# PiPowerHat.net
KiCad netlist of a schematic drawn in EAGLE
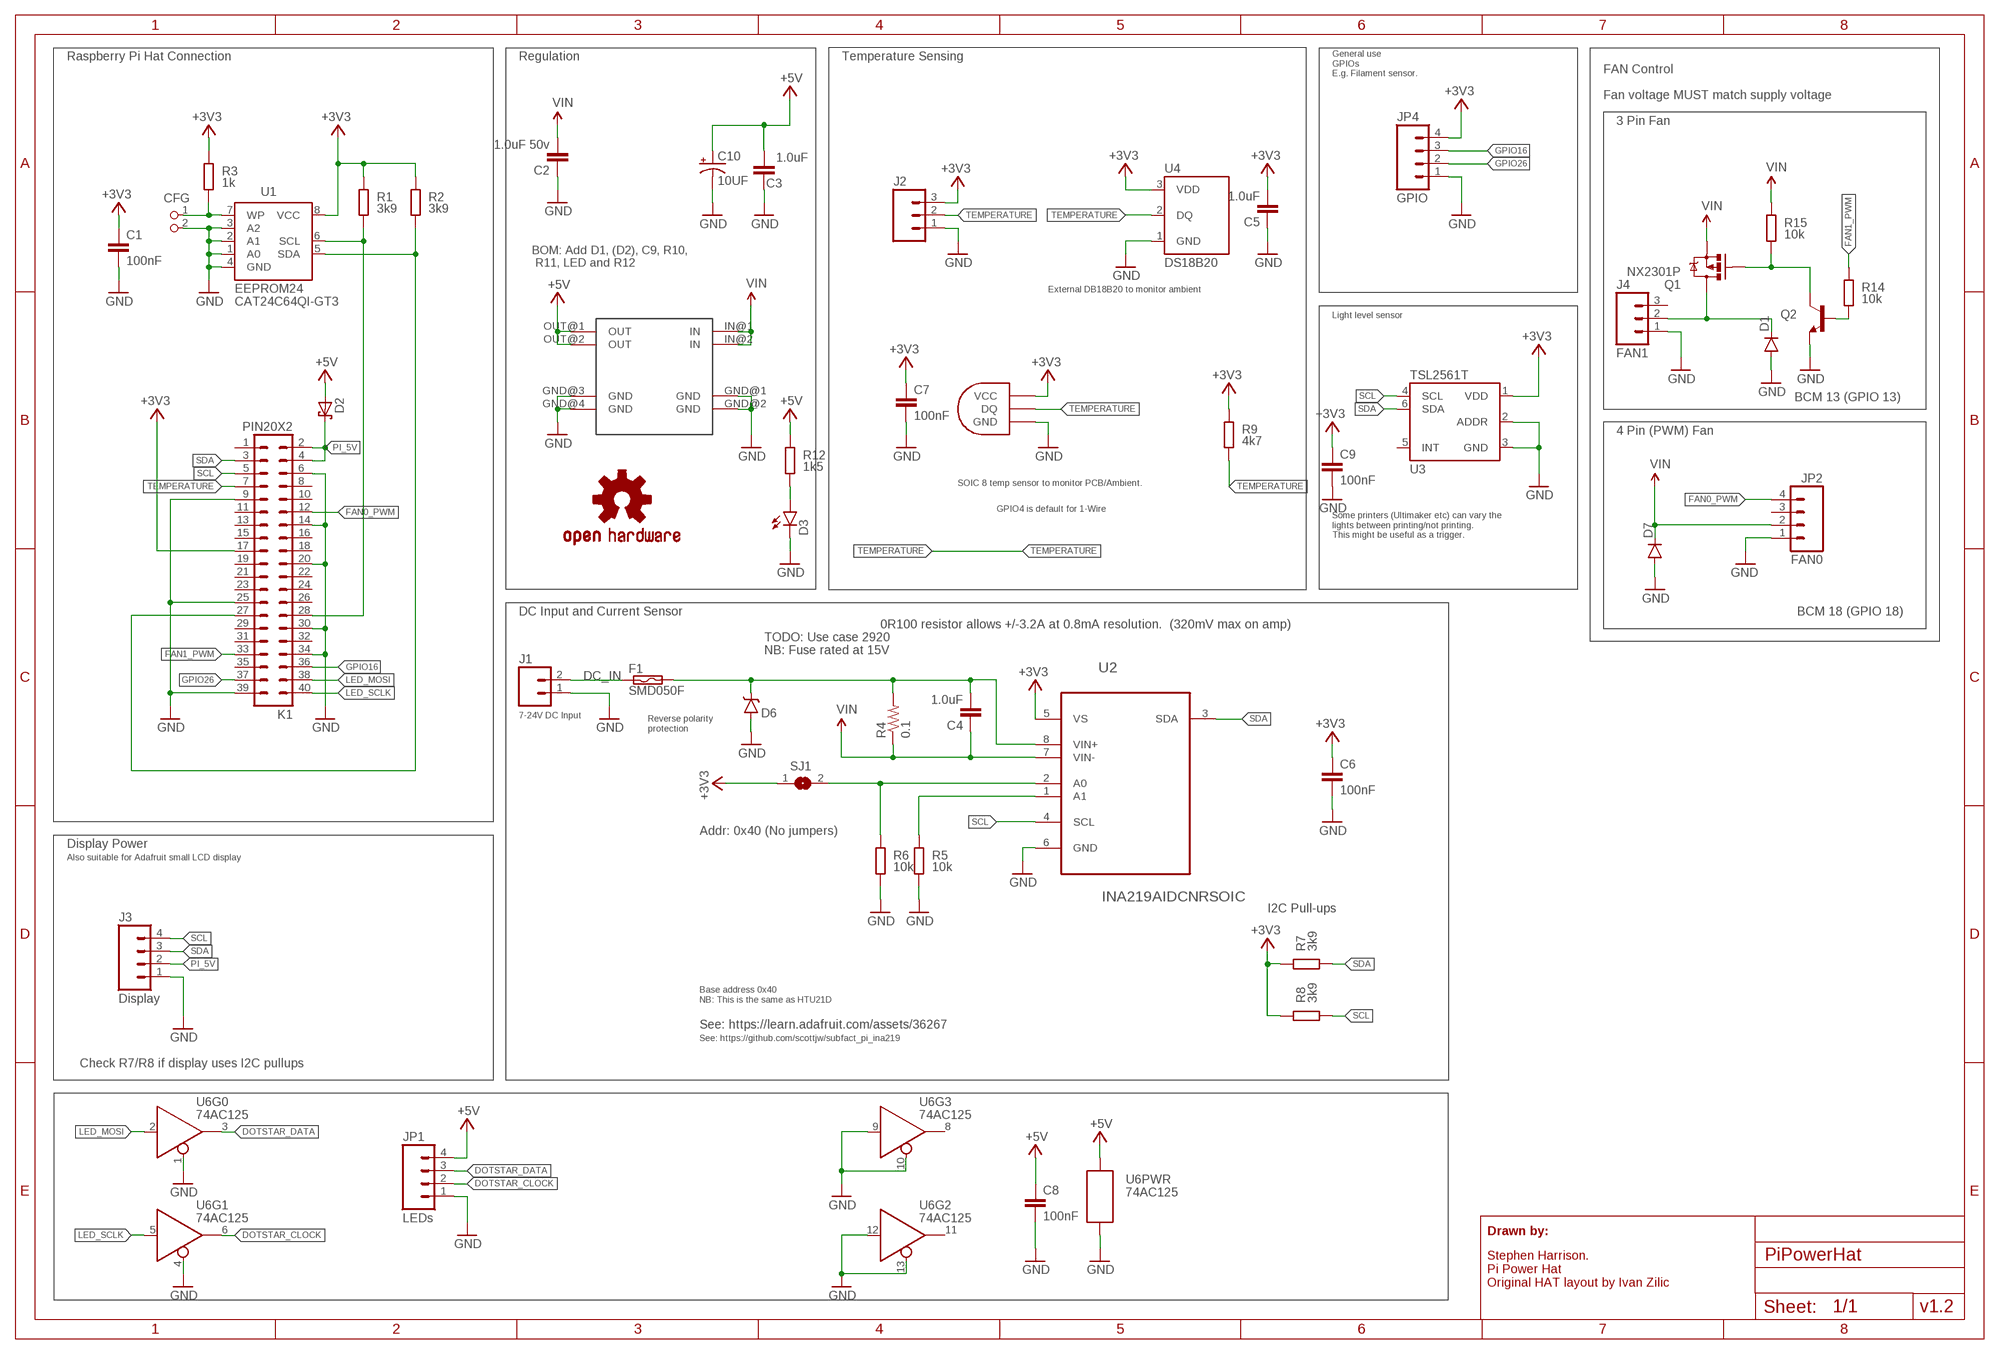
[diagram p0: schematic, sheet 1]

(export (version "E")
  (design (tool "Eeschema 10.0.6"))
  (components
    (comp (ref "C1")
      (value "100nF")
      (footprint "eagle-import:C0805K")
      (libsource (lib "eagle-import") (part "C-EUC0805K"))
    )
    (comp (ref "C2")
      (value "1.0uF 50v")
      (footprint "eagle-import:0805-CAP")
      (libsource (lib "eagle-import") (part "1.0UF-25V-+80/-20(0805){dblquote}"))
    )
    (comp (ref "C3")
      (value "1.0uF")
      (footprint "eagle-import:0805-CAP")
      (libsource (lib "eagle-import") (part "1.0UF-25V-+80/-20(0805){dblquote}"))
    )
    (comp (ref "C4")
      (value "1.0uF")
      (footprint "eagle-import:0805-CAP")
      (libsource (lib "eagle-import") (part "1.0UF-25V-+80/-20(0805){dblquote}"))
    )
    (comp (ref "C5")
      (value "1.0uF")
      (footprint "eagle-import:0805-CAP")
      (libsource (lib "eagle-import") (part "1.0UF-25V-+80/-20(0805){dblquote}"))
    )
    (comp (ref "C6")
      (value "100nF")
      (footprint "eagle-import:C0805K")
      (libsource (lib "eagle-import") (part "C-EUC0805K"))
    )
    (comp (ref "C7")
      (value "100nF")
      (footprint "eagle-import:C0805K")
      (libsource (lib "eagle-import") (part "C-EUC0805K"))
    )
    (comp (ref "C8")
      (value "100nF")
      (footprint "eagle-import:C0805K")
      (libsource (lib "eagle-import") (part "C-EUC0805K"))
    )
    (comp (ref "C9")
      (value "100nF")
      (footprint "eagle-import:C0805K")
      (libsource (lib "eagle-import") (part "C-EUC0805K"))
    )
    (comp (ref "C10")
      (value "10UF")
      (footprint "eagle-import:EIA6032-NOM")
      (libsource (lib "eagle-import") (part "10UF-25V-10%(SMT-TANT)"))
    )
    (comp (ref "CFG")
      (value "PIN2_100")
      (footprint "eagle-import:PIN_W_2")
      (libsource (lib "eagle-import") (part "PIN2_100"))
    )
    (comp (ref "D1")
      (value "DIODESOD123")
      (footprint "eagle-import:SOD-123")
      (libsource (lib "eagle-import") (part "DIODESOD123"))
    )
    (comp (ref "D2")
      (value "MBRS340T3G")
      (footprint "eagle-import:SMC")
      (libsource (lib "eagle-import") (part "SCHOTTKY-DIODESMC"))
    )
    (comp (ref "D3")
      (value "LED1206-BOTTOM")
      (footprint "eagle-import:LED-1206-BOTTOM")
      (libsource (lib "eagle-import") (part "LED1206-BOTTOM"))
    )
    (comp (ref "D6")
      (value "B340A")
      (footprint "eagle-import:SMA-DIODE")
      (libsource (lib "eagle-import") (part "DIODE-SCHOTTKY-B340A"))
    )
    (comp (ref "D7")
      (value "DIODESOD123")
      (footprint "eagle-import:SOD-123")
      (libsource (lib "eagle-import") (part "DIODESOD123"))
    )
    (comp (ref "F1")
      (value "SMD050F")
      (footprint "eagle-import:SMD050F")
      (libsource (lib "eagle-import") (part "SMDF050"))
    )
    (comp (ref "J1")
      (value "M025MM")
      (footprint "eagle-import:SCREWTERMINAL-5MM-2")
      (libsource (lib "eagle-import") (part "M025MM"))
    )
    (comp (ref "J2")
      (value "M03POLAR")
      (footprint "eagle-import:MOLEX-1X3")
      (libsource (lib "eagle-import") (part "M03POLAR"))
    )
    (comp (ref "J3")
      (value "Display")
      (footprint "eagle-import:MOLEX-1X4")
      (libsource (lib "eagle-import") (part "M04POLAR"))
    )
    (comp (ref "J4")
      (value "FAN1")
      (footprint "eagle-import:MOLEX-1X3")
      (libsource (lib "eagle-import") (part "M03POLAR"))
    )
    (comp (ref "JP1")
      (value "LEDs")
      (footprint "eagle-import:MOLEX-1X4")
      (libsource (lib "eagle-import") (part "M04POLAR"))
    )
    (comp (ref "JP2")
      (value "FAN0")
      (footprint "eagle-import:MOLEX-1X4")
      (libsource (lib "eagle-import") (part "M04POLAR"))
    )
    (comp (ref "JP4")
      (value "GPIO")
      (footprint "eagle-import:MOLEX-1X4")
      (libsource (lib "eagle-import") (part "M04POLAR"))
    )
    (comp (ref "K1")
      (value "PIN20X2")
      (footprint "eagle-import:PIN_20X2")
      (libsource (lib "eagle-import") (part "PIN20X2"))
    )
    (comp (ref "LOGO1")
      (value "OSHW-LOGOM")
      (footprint "eagle-import:OSHW-LOGO-M")
      (libsource (lib "eagle-import") (part "OSHW-LOGOM"))
    )
    (comp (ref "Q1")
      (value "NX2301P")
      (footprint "eagle-import:SOT23-3")
      (libsource (lib "eagle-import") (part "MOSFET-PCHANNEL"))
    )
    (comp (ref "Q2")
      (value "TRANSISTOR_NPNSOT23-3")
      (footprint "eagle-import:SOT23-3")
      (libsource (lib "eagle-import") (part "TRANSISTOR_NPNSOT23-3"))
    )
    (comp (ref "R1")
      (value "3k9")
      (footprint "eagle-import:M0805")
      (fields (field (name "TOLERANCE") "5%"))
      (libsource (lib "eagle-import") (part "R-EU_M0805"))
    )
    (comp (ref "R2")
      (value "3k9")
      (footprint "eagle-import:M0805")
      (fields (field (name "TOLERANCE") "5%"))
      (libsource (lib "eagle-import") (part "R-EU_M0805"))
    )
    (comp (ref "R3")
      (value "1k")
      (footprint "eagle-import:M0805")
      (fields (field (name "TOLERANCE") "5%"))
      (libsource (lib "eagle-import") (part "R-EU_M0805"))
    )
    (comp (ref "R4")
      (value "0.1")
      (footprint "eagle-import:2512")
      (libsource (lib "eagle-import") (part "0.001OHM-3W-1%(2512)3W/1%"))
    )
    (comp (ref "R5")
      (value "10k")
      (footprint "eagle-import:M0805")
      (fields (field (name "TOLERANCE") "5%"))
      (libsource (lib "eagle-import") (part "R-EU_M0805"))
    )
    (comp (ref "R6")
      (value "10k")
      (footprint "eagle-import:M0805")
      (fields (field (name "TOLERANCE") "5%"))
      (libsource (lib "eagle-import") (part "R-EU_M0805"))
    )
    (comp (ref "R7")
      (value "3k9")
      (footprint "eagle-import:M0805")
      (fields (field (name "TOLERANCE") "5%"))
      (libsource (lib "eagle-import") (part "R-EU_M0805"))
    )
    (comp (ref "R8")
      (value "3k9")
      (footprint "eagle-import:M0805")
      (fields (field (name "TOLERANCE") "5%"))
      (libsource (lib "eagle-import") (part "R-EU_M0805"))
    )
    (comp (ref "R9")
      (value "4k7")
      (footprint "eagle-import:M0805")
      (fields (field (name "TOLERANCE") "5%"))
      (libsource (lib "eagle-import") (part "R-EU_M0805"))
    )
    (comp (ref "R12")
      (value "1k5")
      (footprint "eagle-import:M0805")
      (fields (field (name "TOLERANCE") "5%"))
      (libsource (lib "eagle-import") (part "R-EU_M0805"))
    )
    (comp (ref "R14")
      (value "10k")
      (footprint "eagle-import:M0805")
      (fields (field (name "TOLERANCE") "5%"))
      (libsource (lib "eagle-import") (part "R-EU_M0805"))
    )
    (comp (ref "R15")
      (value "10k")
      (footprint "eagle-import:M0805")
      (fields (field (name "TOLERANCE") "5%"))
      (libsource (lib "eagle-import") (part "R-EU_M0805"))
    )
    (comp (ref "SJ1") (value "SJ") (footprint "eagle-import:SJ") (libsource (lib "eagle-import") (part "SJ")))
    (comp (ref "U$1")
      (value "MINI-BUCK-MODULE-3A")
      (footprint "eagle-import:MINI-BUCK-MODULE-3A")
      (libsource (lib "eagle-import") (part "MINI-BUCK-MODULE-3A"))
    )
    (comp (ref "U1")
      (value "EEPROM24")
      (footprint "eagle-import:SOIC8")
      (libsource (lib "eagle-import") (part "EEPROM24"))
    )
    (comp (ref "U2")
      (value "INA219AIDCNRSOIC")
      (footprint "eagle-import:SO08")
      (libsource (lib "eagle-import") (part "INA219AIDCNRSOIC"))
    )
    (comp (ref "U3")
      (value "TSL2561T")
      (footprint "eagle-import:TMB-6")
      (libsource (lib "eagle-import") (part "TSL2561T"))
    )
    (comp (ref "U4")
      (value "DS18B20")
      (footprint "eagle-import:TO-92-AMMO")
      (libsource (lib "eagle-import") (part "DS18B20"))
    )
    (comp (ref "U5")
      (value "DS1820SOIC")
      (footprint "eagle-import:DS18B20_SOIC")
      (libsource (lib "eagle-import") (part "DS1820SOIC"))
    )
    (comp (ref "U6")
      (value "74AC125")
      (footprint "eagle-import:SO14")
      (libsource (lib "eagle-import") (part "74125AC125DG"))
    )
  )
  (nets
    (net (code "1") (name "+3V3") (class "Default")
      (node (ref "C1") (pin "1") (pinfunction "1_1") (pintype "passive"))
      (node (ref "C5") (pin "2") (pinfunction "2_2") (pintype "passive"))
      (node (ref "C6") (pin "1") (pinfunction "1_1") (pintype "passive"))
      (node (ref "C7") (pin "1") (pinfunction "1_1") (pintype "passive"))
      (node (ref "C9") (pin "1") (pinfunction "1_1") (pintype "passive"))
      (node (ref "J2") (pin "3") (pinfunction "3_3") (pintype "passive"))
      (node (ref "JP4") (pin "4") (pinfunction "4_4") (pintype "passive"))
      (node (ref "K1") (pin "17") (pinfunction "17_17") (pintype "passive"))
      (node (ref "R1") (pin "2") (pinfunction "2_2") (pintype "passive"))
      (node (ref "R2") (pin "2") (pinfunction "2_2") (pintype "passive"))
      (node (ref "R3") (pin "2") (pinfunction "2_2") (pintype "passive"))
      (node (ref "R7") (pin "2") (pinfunction "2_2") (pintype "passive"))
      (node (ref "R8") (pin "2") (pinfunction "2_2") (pintype "passive"))
      (node (ref "R9") (pin "2") (pinfunction "2_2") (pintype "passive"))
      (node (ref "SJ1") (pin "1") (pinfunction "1_1") (pintype "passive"))
      (node (ref "U1") (pin "8") (pinfunction "VCC_8") (pintype "power_in"))
      (node (ref "U2") (pin "5") (pinfunction "VS_5") (pintype "power_in"))
      (node (ref "U3") (pin "1") (pinfunction "VDD_1") (pintype "power_in"))
      (node (ref "U4") (pin "3") (pinfunction "VDD_3") (pintype "power_in"))
      (node (ref "U5") (pin "VCC") (pinfunction "VCC_VCC") (pintype "power_in"))
    )
    (net (code "2") (name "+5V") (class "Default")
      (node (ref "C10") (pin "A") (pinfunction "+_A") (pintype "passive"))
      (node (ref "C3") (pin "2") (pinfunction "2_2") (pintype "passive"))
      (node (ref "C8") (pin "1") (pinfunction "1_1") (pintype "passive"))
      (node (ref "D2") (pin "A") (pinfunction "A_A") (pintype "passive"))
      (node (ref "JP1") (pin "4") (pinfunction "4_4") (pintype "passive"))
      (node (ref "R12") (pin "2") (pinfunction "2_2") (pintype "passive"))
      (node (ref "U$1") (pin "OUT@1") (pinfunction "OUT_OUT@1") (pintype "bidirectional"))
      (node (ref "U$1") (pin "OUT@2") (pinfunction "OUT_OUT@2") (pintype "bidirectional"))
      (node (ref "U6") (pin "14") (pinfunction "P$V+_14") (pintype "bidirectional"))
    )
    (net (code "3") (name "/DC_IN") (class "Default")
      (node (ref "F1") (pin "1") (pinfunction "1_1") (pintype "passive"))
      (node (ref "J1") (pin "2") (pinfunction "2_2") (pintype "passive"))
    )
    (net (code "4") (name "DOTSTAR_CLOCK") (class "Default")
      (node (ref "JP1") (pin "2") (pinfunction "2_2") (pintype "passive"))
      (node (ref "U6") (pin "6") (pinfunction "Q_6") (pintype "bidirectional"))
    )
    (net (code "5") (name "DOTSTAR_DATA") (class "Default")
      (node (ref "JP1") (pin "3") (pinfunction "3_3") (pintype "passive"))
      (node (ref "U6") (pin "3") (pinfunction "Q_3") (pintype "bidirectional"))
    )
    (net (code "6") (name "FAN0_PWM") (class "Default")
      (node (ref "JP2") (pin "4") (pinfunction "4_4") (pintype "passive"))
      (node (ref "K1") (pin "12") (pinfunction "12_12") (pintype "passive"))
    )
    (net (code "7") (name "FAN1_PWM") (class "Default")
      (node (ref "K1") (pin "33") (pinfunction "33_33") (pintype "passive"))
      (node (ref "R14") (pin "2") (pinfunction "2_2") (pintype "passive"))
    )
    (net (code "8") (name "GND") (class "Default")
      (node (ref "C1") (pin "2") (pinfunction "2_2") (pintype "passive"))
      (node (ref "C10") (pin "C") (pinfunction "-_C") (pintype "passive"))
      (node (ref "C2") (pin "1") (pinfunction "1_1") (pintype "passive"))
      (node (ref "C3") (pin "1") (pinfunction "1_1") (pintype "passive"))
      (node (ref "C5") (pin "1") (pinfunction "1_1") (pintype "passive"))
      (node (ref "C6") (pin "2") (pinfunction "2_2") (pintype "passive"))
      (node (ref "C7") (pin "2") (pinfunction "2_2") (pintype "passive"))
      (node (ref "C8") (pin "2") (pinfunction "2_2") (pintype "passive"))
      (node (ref "C9") (pin "2") (pinfunction "2_2") (pintype "passive"))
      (node (ref "CFG") (pin "2") (pinfunction "2_2") (pintype "passive"))
      (node (ref "D1") (pin "A") (pinfunction "A_A") (pintype "passive"))
      (node (ref "D3") (pin "C") (pinfunction "C_C") (pintype "passive"))
      (node (ref "D6") (pin "A") (pinfunction "A_A") (pintype "passive"))
      (node (ref "D7") (pin "A") (pinfunction "A_A") (pintype "passive"))
      (node (ref "J1") (pin "1") (pinfunction "1_1") (pintype "passive"))
      (node (ref "J2") (pin "1") (pinfunction "1_1") (pintype "passive"))
      (node (ref "J3") (pin "1") (pinfunction "1_1") (pintype "passive"))
      (node (ref "J4") (pin "1") (pinfunction "1_1") (pintype "passive"))
      (node (ref "JP1") (pin "1") (pinfunction "1_1") (pintype "passive"))
      (node (ref "JP2") (pin "1") (pinfunction "1_1") (pintype "passive"))
      (node (ref "JP4") (pin "1") (pinfunction "1_1") (pintype "passive"))
      (node (ref "K1") (pin "14") (pinfunction "14_14") (pintype "passive"))
      (node (ref "K1") (pin "20") (pinfunction "20_20") (pintype "passive"))
      (node (ref "K1") (pin "25") (pinfunction "25_25") (pintype "passive"))
      (node (ref "K1") (pin "30") (pinfunction "30_30") (pintype "passive"))
      (node (ref "K1") (pin "34") (pinfunction "34_34") (pintype "passive"))
      (node (ref "K1") (pin "39") (pinfunction "39_39") (pintype "passive"))
      (node (ref "K1") (pin "6") (pinfunction "6_6") (pintype "passive"))
      (node (ref "K1") (pin "9") (pinfunction "9_9") (pintype "passive"))
      (node (ref "Q2") (pin "2") (pinfunction "E_2") (pintype "passive"))
      (node (ref "R5") (pin "1") (pinfunction "1_1") (pintype "passive"))
      (node (ref "R6") (pin "1") (pinfunction "1_1") (pintype "passive"))
      (node (ref "U$1") (pin "GND@1") (pinfunction "GND_GND@1") (pintype "bidirectional"))
      (node (ref "U$1") (pin "GND@2") (pinfunction "GND_GND@2") (pintype "bidirectional"))
      (node (ref "U$1") (pin "GND@3") (pinfunction "GND_GND@3") (pintype "bidirectional"))
      (node (ref "U$1") (pin "GND@4") (pinfunction "GND_GND@4") (pintype "bidirectional"))
      (node (ref "U1") (pin "1") (pinfunction "A0_1") (pintype "input"))
      (node (ref "U1") (pin "2") (pinfunction "A1_2") (pintype "input"))
      (node (ref "U1") (pin "3") (pinfunction "A2_3") (pintype "input"))
      (node (ref "U1") (pin "4") (pinfunction "GND_4") (pintype "power_in"))
      (node (ref "U2") (pin "6") (pinfunction "GND_6") (pintype "passive"))
      (node (ref "U3") (pin "2") (pinfunction "ADDR_2") (pintype "input"))
      (node (ref "U3") (pin "3") (pinfunction "GND_3") (pintype "power_in"))
      (node (ref "U4") (pin "1") (pinfunction "GND_1") (pintype "power_in"))
      (node (ref "U5") (pin "GND") (pinfunction "GND_GND") (pintype "power_in"))
      (node (ref "U6") (pin "1") (pinfunction "~{EN}_1") (pintype "bidirectional"))
      (node (ref "U6") (pin "10") (pinfunction "~{EN}_10") (pintype "bidirectional"))
      (node (ref "U6") (pin "12") (pinfunction "D_12") (pintype "bidirectional"))
      (node (ref "U6") (pin "13") (pinfunction "~{EN}_13") (pintype "bidirectional"))
      (node (ref "U6") (pin "4") (pinfunction "~{EN}_4") (pintype "bidirectional"))
      (node (ref "U6") (pin "7") (pinfunction "P$V-_7") (pintype "bidirectional"))
      (node (ref "U6") (pin "9") (pinfunction "D_9") (pintype "bidirectional"))
    )
    (net (code "9") (name "GPIO16") (class "Default")
      (node (ref "JP4") (pin "3") (pinfunction "3_3") (pintype "passive"))
      (node (ref "K1") (pin "36") (pinfunction "36_36") (pintype "passive"))
    )
    (net (code "10") (name "GPIO26") (class "Default")
      (node (ref "JP4") (pin "2") (pinfunction "2_2") (pintype "passive"))
      (node (ref "K1") (pin "37") (pinfunction "37_37") (pintype "passive"))
    )
    (net (code "11") (name "LED_MOSI") (class "Default")
      (node (ref "K1") (pin "38") (pinfunction "38_38") (pintype "passive"))
      (node (ref "U6") (pin "2") (pinfunction "D_2") (pintype "bidirectional"))
    )
    (net (code "12") (name "LED_SCLK") (class "Default")
      (node (ref "K1") (pin "40") (pinfunction "40_40") (pintype "passive"))
      (node (ref "U6") (pin "5") (pinfunction "D_5") (pintype "bidirectional"))
    )
    (net (code "13") (name "Net-(D3-PadA)") (class "Default")
      (node (ref "D3") (pin "A") (pinfunction "A_A") (pintype "passive"))
      (node (ref "R12") (pin "1") (pinfunction "1_1") (pintype "passive"))
    )
    (net (code "14") (name "Net-(Q1-D)") (class "Default")
      (node (ref "D1") (pin "C") (pinfunction "C_C") (pintype "passive"))
      (node (ref "J4") (pin "2") (pinfunction "2_2") (pintype "passive"))
      (node (ref "Q1") (pin "3") (pinfunction "D_3") (pintype "passive"))
    )
    (net (code "15") (name "Net-(Q1-G)") (class "Default")
      (node (ref "Q1") (pin "1") (pinfunction "G_1") (pintype "passive"))
      (node (ref "Q2") (pin "3") (pinfunction "C_3") (pintype "passive"))
      (node (ref "R15") (pin "1") (pinfunction "1_1") (pintype "passive"))
    )
    (net (code "16") (name "Net-(Q2-B)") (class "Default")
      (node (ref "Q2") (pin "1") (pinfunction "B_1") (pintype "passive"))
      (node (ref "R14") (pin "1") (pinfunction "1_1") (pintype "passive"))
    )
    (net (code "17") (name "Net-(U1-SCL)") (class "Default")
      (node (ref "K1") (pin "28") (pinfunction "28_28") (pintype "passive"))
      (node (ref "R1") (pin "1") (pinfunction "1_1") (pintype "passive"))
      (node (ref "U1") (pin "6") (pinfunction "SCL_6") (pintype "input"))
    )
    (net (code "18") (name "Net-(U1-SDA)") (class "Default")
      (node (ref "K1") (pin "27") (pinfunction "27_27") (pintype "passive"))
      (node (ref "R2") (pin "1") (pinfunction "1_1") (pintype "passive"))
      (node (ref "U1") (pin "5") (pinfunction "SDA_5") (pintype "bidirectional"))
    )
    (net (code "19") (name "Net-(U1-WP)") (class "Default")
      (node (ref "CFG") (pin "1") (pinfunction "1_1") (pintype "passive"))
      (node (ref "R3") (pin "1") (pinfunction "1_1") (pintype "passive"))
      (node (ref "U1") (pin "7") (pinfunction "WP_7") (pintype "input"))
    )
    (net (code "20") (name "Net-(U2-A0)") (class "Default")
      (node (ref "R6") (pin "2") (pinfunction "2_2") (pintype "passive"))
      (node (ref "SJ1") (pin "2") (pinfunction "2_2") (pintype "passive"))
      (node (ref "U2") (pin "2") (pinfunction "A0_2") (pintype "input"))
    )
    (net (code "21") (name "Net-(U2-A1)") (class "Default")
      (node (ref "R5") (pin "2") (pinfunction "2_2") (pintype "passive"))
      (node (ref "U2") (pin "1") (pinfunction "A1_1") (pintype "input"))
    )
    (net (code "22") (name "Net-(U2-VIN+)") (class "Default")
      (node (ref "C4") (pin "2") (pinfunction "2_2") (pintype "passive"))
      (node (ref "D6") (pin "C") (pinfunction "C_C") (pintype "passive"))
      (node (ref "F1") (pin "2") (pinfunction "2_2") (pintype "passive"))
      (node (ref "R4") (pin "2") (pinfunction "2_2") (pintype "passive"))
      (node (ref "U2") (pin "8") (pinfunction "VIN+_8") (pintype "input"))
    )
    (net (code "23") (name "PI_5V") (class "Default")
      (node (ref "D2") (pin "C") (pinfunction "C_C") (pintype "passive"))
      (node (ref "J3") (pin "2") (pinfunction "2_2") (pintype "passive"))
      (node (ref "K1") (pin "2") (pinfunction "2_2") (pintype "passive"))
      (node (ref "K1") (pin "4") (pinfunction "4_4") (pintype "passive"))
    )
    (net (code "24") (name "SCL") (class "Default")
      (node (ref "J3") (pin "4") (pinfunction "4_4") (pintype "passive"))
      (node (ref "K1") (pin "5") (pinfunction "5_5") (pintype "passive"))
      (node (ref "R8") (pin "1") (pinfunction "1_1") (pintype "passive"))
      (node (ref "U2") (pin "4") (pinfunction "SCL_4") (pintype "input"))
      (node (ref "U3") (pin "4") (pinfunction "SCL_4") (pintype "input"))
    )
    (net (code "25") (name "SDA") (class "Default")
      (node (ref "J3") (pin "3") (pinfunction "3_3") (pintype "passive"))
      (node (ref "K1") (pin "3") (pinfunction "3_3") (pintype "passive"))
      (node (ref "R7") (pin "1") (pinfunction "1_1") (pintype "passive"))
      (node (ref "U2") (pin "3") (pinfunction "SDA_3") (pintype "bidirectional"))
      (node (ref "U3") (pin "6") (pinfunction "SDA_6") (pintype "bidirectional"))
    )
    (net (code "26") (name "TEMPERATURE") (class "Default")
      (node (ref "J2") (pin "2") (pinfunction "2_2") (pintype "passive"))
      (node (ref "K1") (pin "7") (pinfunction "7_7") (pintype "passive"))
      (node (ref "R9") (pin "1") (pinfunction "1_1") (pintype "passive"))
      (node (ref "U4") (pin "2") (pinfunction "DQ_2") (pintype "bidirectional"))
      (node (ref "U5") (pin "DQ") (pinfunction "DQ_DQ") (pintype "bidirectional"))
    )
    (net (code "27") (name "VIN") (class "Default")
      (node (ref "C2") (pin "2") (pinfunction "2_2") (pintype "passive"))
      (node (ref "C4") (pin "1") (pinfunction "1_1") (pintype "passive"))
      (node (ref "D7") (pin "C") (pinfunction "C_C") (pintype "passive"))
      (node (ref "JP2") (pin "2") (pinfunction "2_2") (pintype "passive"))
      (node (ref "Q1") (pin "2") (pinfunction "S_2") (pintype "passive"))
      (node (ref "R15") (pin "2") (pinfunction "2_2") (pintype "passive"))
      (node (ref "R4") (pin "1") (pinfunction "1_1") (pintype "passive"))
      (node (ref "U$1") (pin "IN@1") (pinfunction "IN_IN@1") (pintype "bidirectional"))
      (node (ref "U$1") (pin "IN@2") (pinfunction "IN_IN@2") (pintype "bidirectional"))
      (node (ref "U2") (pin "7") (pinfunction "VIN-_7") (pintype "input"))
    )
    (net (code "28") (name "unconnected-(J4-Pad3)") (class "Default")
      (node (ref "J4") (pin "3") (pinfunction "3_3") (pintype "passive"))
    )
    (net (code "29") (name "unconnected-(JP2-Pad3)") (class "Default")
      (node (ref "JP2") (pin "3") (pinfunction "3_3") (pintype "passive"))
    )
    (net (code "30") (name "unconnected-(K1-Pad1)") (class "Default")
      (node (ref "K1") (pin "1") (pinfunction "1_1") (pintype "passive"))
    )
    (net (code "31") (name "unconnected-(K1-Pad8)") (class "Default")
      (node (ref "K1") (pin "8") (pinfunction "8_8") (pintype "passive"))
    )
    (net (code "32") (name "unconnected-(K1-Pad10)") (class "Default")
      (node (ref "K1") (pin "10") (pinfunction "10_10") (pintype "passive"))
    )
    (net (code "33") (name "unconnected-(K1-Pad11)") (class "Default")
      (node (ref "K1") (pin "11") (pinfunction "11_11") (pintype "passive"))
    )
    (net (code "34") (name "unconnected-(K1-Pad13)") (class "Default")
      (node (ref "K1") (pin "13") (pinfunction "13_13") (pintype "passive"))
    )
    (net (code "35") (name "unconnected-(K1-Pad15)") (class "Default")
      (node (ref "K1") (pin "15") (pinfunction "15_15") (pintype "passive"))
    )
    (net (code "36") (name "unconnected-(K1-Pad16)") (class "Default")
      (node (ref "K1") (pin "16") (pinfunction "16_16") (pintype "passive"))
    )
    (net (code "37") (name "unconnected-(K1-Pad18)") (class "Default")
      (node (ref "K1") (pin "18") (pinfunction "18_18") (pintype "passive"))
    )
    (net (code "38") (name "unconnected-(K1-Pad19)") (class "Default")
      (node (ref "K1") (pin "19") (pinfunction "19_19") (pintype "passive"))
    )
    (net (code "39") (name "unconnected-(K1-Pad21)") (class "Default")
      (node (ref "K1") (pin "21") (pinfunction "21_21") (pintype "passive"))
    )
    (net (code "40") (name "unconnected-(K1-Pad22)") (class "Default")
      (node (ref "K1") (pin "22") (pinfunction "22_22") (pintype "passive"))
    )
    (net (code "41") (name "unconnected-(K1-Pad23)") (class "Default")
      (node (ref "K1") (pin "23") (pinfunction "23_23") (pintype "passive"))
    )
    (net (code "42") (name "unconnected-(K1-Pad24)") (class "Default")
      (node (ref "K1") (pin "24") (pinfunction "24_24") (pintype "passive"))
    )
    (net (code "43") (name "unconnected-(K1-Pad26)") (class "Default")
      (node (ref "K1") (pin "26") (pinfunction "26_26") (pintype "passive"))
    )
    (net (code "44") (name "unconnected-(K1-Pad29)") (class "Default")
      (node (ref "K1") (pin "29") (pinfunction "29_29") (pintype "passive"))
    )
    (net (code "45") (name "unconnected-(K1-Pad31)") (class "Default")
      (node (ref "K1") (pin "31") (pinfunction "31_31") (pintype "passive"))
    )
    (net (code "46") (name "unconnected-(K1-Pad32)") (class "Default")
      (node (ref "K1") (pin "32") (pinfunction "32_32") (pintype "passive"))
    )
    (net (code "47") (name "unconnected-(K1-Pad35)") (class "Default")
      (node (ref "K1") (pin "35") (pinfunction "35_35") (pintype "passive"))
    )
    (net (code "48") (name "unconnected-(U3-INT-Pad5)") (class "Default")
      (node (ref "U3") (pin "5") (pinfunction "INT_5") (pintype "output"))
    )
    (net (code "49") (name "unconnected-(U6C-Q-Pad11)") (class "Default")
      (node (ref "U6") (pin "11") (pinfunction "Q_11") (pintype "bidirectional"))
    )
    (net (code "50") (name "unconnected-(U6D-Q-Pad8)") (class "Default")
      (node (ref "U6") (pin "8") (pinfunction "Q_8") (pintype "bidirectional"))
    )
  )
)
